# mbmc_single_board_cpu.net
KiCad netlist of a schematic drawn in EAGLE
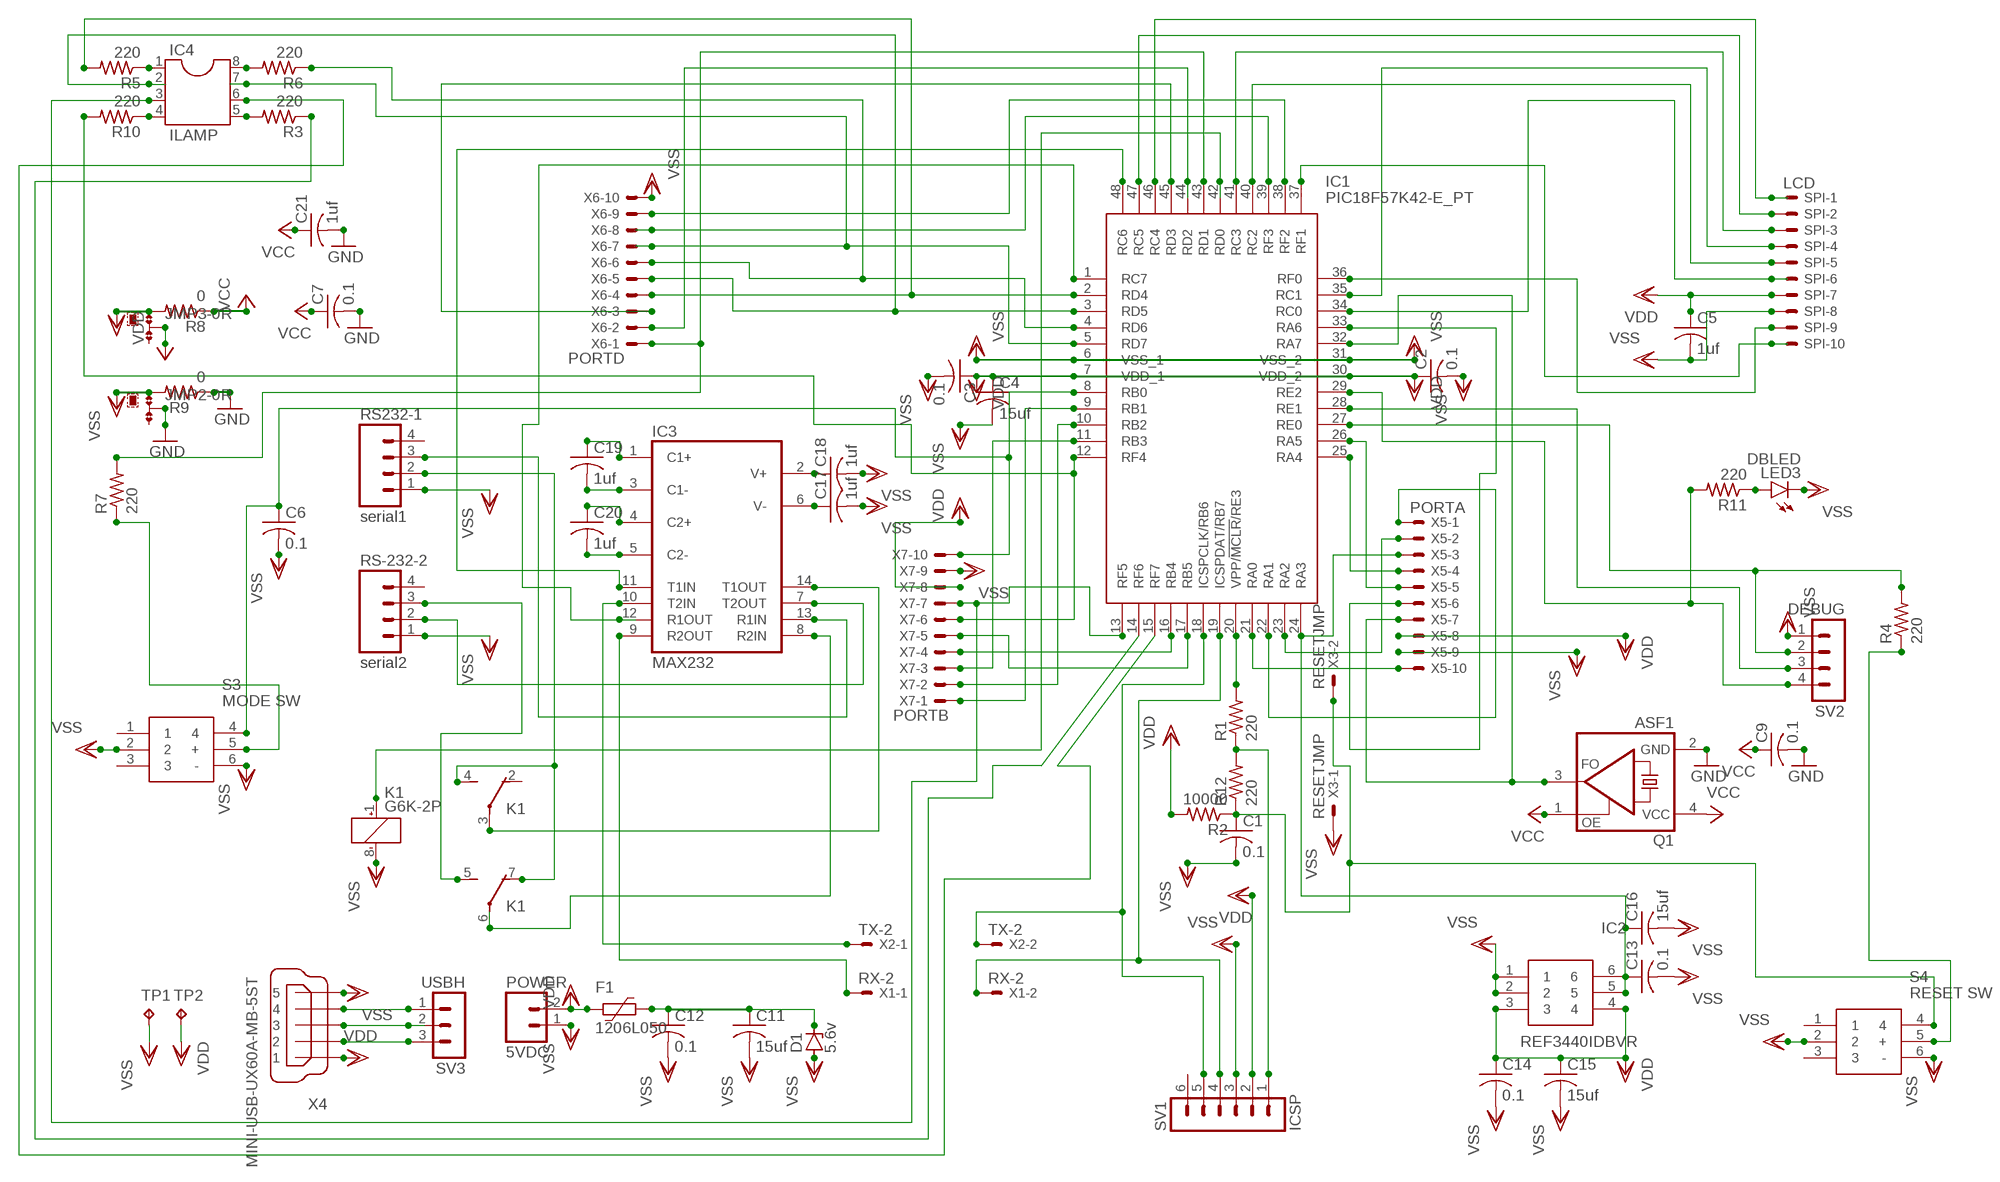
[diagram p0: schematic, sheet 1]

(export (version "E")
  (design (tool "Eeschema 10.0.6"))
  (components
    (comp (ref "C1")
      (value "0.1")
      (footprint "eagle-import:C1206")
      (libsource (lib "eagle-import") (part "C-USC1206"))
    )
    (comp (ref "C2")
      (value "0.1")
      (footprint "eagle-import:C1206")
      (libsource (lib "eagle-import") (part "C-USC1206"))
    )
    (comp (ref "C3")
      (value "0.1")
      (footprint "eagle-import:C1206")
      (libsource (lib "eagle-import") (part "C-USC1206"))
    )
    (comp (ref "C4")
      (value "15uf")
      (footprint "eagle-import:C1206")
      (libsource (lib "eagle-import") (part "C-USC1206"))
    )
    (comp (ref "C5")
      (value "1uf")
      (footprint "eagle-import:C0805")
      (libsource (lib "eagle-import") (part "C-USC0805"))
    )
    (comp (ref "C6")
      (value "0.1")
      (footprint "eagle-import:C1206")
      (libsource (lib "eagle-import") (part "C-USC1206"))
    )
    (comp (ref "C7")
      (value "0.1")
      (footprint "eagle-import:C1206")
      (libsource (lib "eagle-import") (part "C-USC1206"))
    )
    (comp (ref "C9")
      (value "0.1")
      (footprint "eagle-import:C1206")
      (libsource (lib "eagle-import") (part "C-USC1206"))
    )
    (comp (ref "C11")
      (value "15uf")
      (footprint "eagle-import:C1206")
      (libsource (lib "eagle-import") (part "C-USC1206"))
    )
    (comp (ref "C12")
      (value "0.1")
      (footprint "eagle-import:C1206")
      (libsource (lib "eagle-import") (part "C-USC1206"))
    )
    (comp (ref "C13")
      (value "0.1")
      (footprint "eagle-import:C1206")
      (libsource (lib "eagle-import") (part "C-USC1206"))
    )
    (comp (ref "C14")
      (value "0.1")
      (footprint "eagle-import:C1206")
      (libsource (lib "eagle-import") (part "C-USC1206"))
    )
    (comp (ref "C15")
      (value "15uf")
      (footprint "eagle-import:C1206")
      (libsource (lib "eagle-import") (part "C-USC1206"))
    )
    (comp (ref "C16")
      (value "15uf")
      (footprint "eagle-import:C1206")
      (libsource (lib "eagle-import") (part "C-USC1206"))
    )
    (comp (ref "C17")
      (value "1uf")
      (footprint "eagle-import:C0805")
      (libsource (lib "eagle-import") (part "C-USC0805"))
    )
    (comp (ref "C18")
      (value "1uf")
      (footprint "eagle-import:C0805")
      (libsource (lib "eagle-import") (part "C-USC0805"))
    )
    (comp (ref "C19")
      (value "1uf")
      (footprint "eagle-import:C0805")
      (libsource (lib "eagle-import") (part "C-USC0805"))
    )
    (comp (ref "C20")
      (value "1uf")
      (footprint "eagle-import:C0805")
      (libsource (lib "eagle-import") (part "C-USC0805"))
    )
    (comp (ref "C21")
      (value "1uf")
      (footprint "eagle-import:C0805")
      (libsource (lib "eagle-import") (part "C-USC0805"))
    )
    (comp (ref "D1")
      (value "5.6v")
      (footprint "eagle-import:DO34Z7")
      (libsource (lib "eagle-import") (part "ZENER-DIODEDO34-7"))
    )
    (comp (ref "F1")
      (value "1206L050")
      (footprint "eagle-import:1206L")
      (fields (field (name "MF") "Littelfuse"))
      (libsource (lib "eagle-import") (part "?1206L050"))
    )
    (comp (ref "IC1")
      (value "PIC18F57K42-E_PT")
      (footprint "eagle-import:QFP50P900X900X120-48N")
      (fields
        (field (name "MANUFACTURER_PART_NUMBER") "PIC18F57K42-E/PT")
        (field (name "MOUSER_PART_NUMBER") "579-PIC18F57K42-E/PT")
      )
      (libsource (lib "eagle-import") (part "PIC18F57K42-E_PT"))
    )
    (comp (ref "IC2")
      (value "REF3440IDBVR")
      (footprint "eagle-import:SOP95P280X145-6N")
      (libsource (lib "eagle-import") (part "REF3440IDBVR"))
    )
    (comp (ref "IC3")
      (value "MAX232")
      (footprint "eagle-import:DIL16")
      (fields (field (name "MF") "MAXIM") (field (name "MPN") "MAX232ACPE+"))
      (libsource (lib "eagle-import") (part "MAX232"))
    )
    (comp (ref "IC4")
      (value "ILAMP")
      (footprint "eagle-import:SOCKET-08")
      (libsource (lib "eagle-import") (part "DIL8S"))
    )
    (comp (ref "JMP2")
      (value "0R-JUMPA")
      (footprint "eagle-import:A0R-JMP")
      (libsource (lib "eagle-import") (part "0R-JUMPA"))
    )
    (comp (ref "JMP3")
      (value "0R-JUMPA")
      (footprint "eagle-import:A0R-JMP")
      (libsource (lib "eagle-import") (part "0R-JUMPA"))
    )
    (comp (ref "K1")
      (value "G6K-2P")
      (footprint "eagle-import:G6K-2P")
      (fields (field (name "MF") "OMRON COMPONENTS USA") (field (name "MPN") "G6K-2P DC3"))
      (libsource (lib "eagle-import") (part "G6K-2P"))
    )
    (comp (ref "LED3")
      (value "DBLED")
      (footprint "eagle-import:CHIPLED_1206")
      (libsource (lib "eagle-import") (part "LEDCHIPLED_1206"))
    )
    (comp (ref "POWER")
      (value "5VDC")
      (footprint "eagle-import:02P")
      (libsource (lib "eagle-import") (part "M02"))
    )
    (comp (ref "Q1")
      (value "ASF1")
      (footprint "eagle-import:ASF")
      (libsource (lib "eagle-import") (part "ASF1"))
    )
    (comp (ref "R1")
      (value "220")
      (footprint "eagle-import:R1206")
      (libsource (lib "eagle-import") (part "R-US_R1206"))
    )
    (comp (ref "R2")
      (value "10000")
      (footprint "eagle-import:R1206")
      (libsource (lib "eagle-import") (part "R-US_R1206"))
    )
    (comp (ref "R3")
      (value "220")
      (footprint "eagle-import:R1206")
      (libsource (lib "eagle-import") (part "R-US_R1206"))
    )
    (comp (ref "R4")
      (value "220")
      (footprint "eagle-import:R1206")
      (libsource (lib "eagle-import") (part "R-US_R1206"))
    )
    (comp (ref "R5")
      (value "220")
      (footprint "eagle-import:R1206")
      (libsource (lib "eagle-import") (part "R-US_R1206"))
    )
    (comp (ref "R6")
      (value "220")
      (footprint "eagle-import:R1206")
      (libsource (lib "eagle-import") (part "R-US_R1206"))
    )
    (comp (ref "R7")
      (value "220")
      (footprint "eagle-import:R1206")
      (libsource (lib "eagle-import") (part "R-US_R1206"))
    )
    (comp (ref "R8")
      (value "0")
      (footprint "eagle-import:R1206")
      (libsource (lib "eagle-import") (part "R-US_R1206"))
    )
    (comp (ref "R9")
      (value "0")
      (footprint "eagle-import:R1206")
      (libsource (lib "eagle-import") (part "R-US_R1206"))
    )
    (comp (ref "R10")
      (value "220")
      (footprint "eagle-import:R1206")
      (libsource (lib "eagle-import") (part "R-US_R1206"))
    )
    (comp (ref "R11")
      (value "220")
      (footprint "eagle-import:R1206")
      (libsource (lib "eagle-import") (part "R-US_R1206"))
    )
    (comp (ref "R12")
      (value "220")
      (footprint "eagle-import:R1206")
      (libsource (lib "eagle-import") (part "R-US_R1206"))
    )
    (comp (ref "RS-232-2")
      (value "serial2")
      (footprint "eagle-import:04P")
      (libsource (lib "eagle-import") (part "M04"))
    )
    (comp (ref "RS232-1")
      (value "serial1")
      (footprint "eagle-import:04P")
      (libsource (lib "eagle-import") (part "M04"))
    )
    (comp (ref "S3")
      (value "MODE SW")
      (footprint "eagle-import:B3W-9_1-LED")
      (fields
        (field (name "MANUFACTURER_PART_NUMBER") "B3W-9000-Y1N")
        (field (name "MOUSER_PART_NUMBER") "653-B3W-9000-Y1N")
        (field (name "RS_PART_NUMBER") "0492777P")
      )
      (libsource (lib "eagle-import") (part "B3W-9000-Y1N"))
    )
    (comp (ref "S4")
      (value "RESET SW")
      (footprint "eagle-import:B3W-9_1-LED")
      (fields
        (field (name "MANUFACTURER_PART_NUMBER") "B3W-9000-Y1N")
        (field (name "MOUSER_PART_NUMBER") "653-B3W-9000-Y1N")
        (field (name "RS_PART_NUMBER") "0492777P")
      )
      (libsource (lib "eagle-import") (part "B3W-9000-Y1N"))
    )
    (comp (ref "SPI")
      (value "LCD")
      (footprint "eagle-import:22-23-2101")
      (fields (field (name "MF") "MOLEX") (field (name "MPN") "22-23-2101"))
      (libsource (lib "eagle-import") (part "22-23-2101"))
    )
    (comp (ref "SV1")
      (value "ICSP")
      (footprint "eagle-import:MA06-1")
      (libsource (lib "eagle-import") (part "MA06-1"))
    )
    (comp (ref "SV2")
      (value "DEBUG")
      (footprint "eagle-import:MA04-1")
      (libsource (lib "eagle-import") (part "MA04-1"))
    )
    (comp (ref "SV3")
      (value "USBH")
      (footprint "eagle-import:MA03-1")
      (libsource (lib "eagle-import") (part "MA03-1"))
    )
    (comp (ref "TP1")
      (value "TPB1,27")
      (footprint "eagle-import:B1,27")
      (libsource (lib "eagle-import") (part "TPB1,27"))
    )
    (comp (ref "TP2")
      (value "TPB1,27")
      (footprint "eagle-import:B1,27")
      (libsource (lib "eagle-import") (part "TPB1,27"))
    )
    (comp (ref "X1")
      (value "RX-2")
      (footprint "eagle-import:332-02")
      (libsource (lib "eagle-import") (part "332-02"))
    )
    (comp (ref "X2")
      (value "TX-2")
      (footprint "eagle-import:332-02")
      (libsource (lib "eagle-import") (part "332-02"))
    )
    (comp (ref "X3")
      (value "RESETJMP")
      (footprint "eagle-import:332-02")
      (libsource (lib "eagle-import") (part "332-02"))
    )
    (comp (ref "X4")
      (value "MINI-USB-UX60A-MB-5ST")
      (footprint "eagle-import:UX60A-MB-5ST")
      (libsource (lib "eagle-import") (part "MINI-USB-UX60A-MB-5ST"))
    )
    (comp (ref "X5")
      (value "PORTA")
      (footprint "eagle-import:22-23-2101")
      (fields (field (name "MF") "MOLEX") (field (name "MPN") "22-23-2101"))
      (libsource (lib "eagle-import") (part "22-23-2101"))
    )
    (comp (ref "X6")
      (value "PORTD")
      (footprint "eagle-import:22-23-2101")
      (fields (field (name "MF") "MOLEX") (field (name "MPN") "22-23-2101"))
      (libsource (lib "eagle-import") (part "22-23-2101"))
    )
    (comp (ref "X7")
      (value "PORTB")
      (footprint "eagle-import:22-23-2101")
      (fields (field (name "MF") "MOLEX") (field (name "MPN") "22-23-2101"))
      (libsource (lib "eagle-import") (part "22-23-2101"))
    )
  )
  (nets
    (net (code "1") (name "GND") (class "Default")
      (node (ref "C21") (pin "2") (pinfunction "2_2") (pintype "passive"))
      (node (ref "C7") (pin "2") (pinfunction "2_2") (pintype "passive"))
      (node (ref "C9") (pin "2") (pinfunction "2_2") (pintype "passive"))
      (node (ref "JMP2") (pin "2") (pinfunction "2_2") (pintype "passive"))
      (node (ref "Q1") (pin "2") (pinfunction "GND_2") (pintype "power_in"))
      (node (ref "R9") (pin "1") (pinfunction "1_1") (pintype "passive"))
    )
    (net (code "2") (name "Net-(C11-Pad1)") (class "Default")
      (node (ref "C11") (pin "1") (pinfunction "1_1") (pintype "passive"))
      (node (ref "C12") (pin "1") (pinfunction "1_1") (pintype "passive"))
      (node (ref "D1") (pin "C") (pinfunction "C_C") (pintype "passive"))
      (node (ref "F1") (pin "1") (pinfunction "1_1") (pintype "passive"))
    )
    (net (code "3") (name "Net-(IC1-ICSPCLK{slash}RB6)") (class "Default")
      (node (ref "IC1") (pin "18") (pinfunction "ICSPCLK/RB6_18") (pintype "bidirectional"))
      (node (ref "SV1") (pin "5") (pinfunction "5_5") (pintype "passive"))
      (node (ref "X2") (pin "2") (pinfunction "S_2") (pintype "passive"))
    )
    (net (code "4") (name "Net-(IC1-ICSPDAT{slash}RB7)") (class "Default")
      (node (ref "IC1") (pin "19") (pinfunction "ICSPDAT/RB7_19") (pintype "bidirectional"))
      (node (ref "SV1") (pin "4") (pinfunction "4_4") (pintype "passive"))
      (node (ref "X1") (pin "2") (pinfunction "S_2") (pintype "passive"))
    )
    (net (code "5") (name "Net-(IC1-RA0)") (class "Default")
      (node (ref "IC1") (pin "21") (pinfunction "RA0_21") (pintype "bidirectional"))
      (node (ref "X5") (pin "10") (pinfunction "S_10") (pintype "passive"))
    )
    (net (code "6") (name "Net-(IC1-RA1)") (class "Default")
      (node (ref "IC1") (pin "22") (pinfunction "RA1_22") (pintype "bidirectional"))
      (node (ref "X5") (pin "1") (pinfunction "S_1") (pintype "passive"))
    )
    (net (code "7") (name "Net-(IC1-RA2)") (class "Default")
      (node (ref "IC1") (pin "23") (pinfunction "RA2_23") (pintype "bidirectional"))
      (node (ref "X5") (pin "2") (pinfunction "S_2") (pintype "passive"))
    )
    (net (code "8") (name "Net-(IC1-RA3)") (class "Default")
      (node (ref "C13") (pin "1") (pinfunction "1_1") (pintype "passive"))
      (node (ref "C16") (pin "1") (pinfunction "1_1") (pintype "passive"))
      (node (ref "IC1") (pin "24") (pinfunction "RA3_24") (pintype "bidirectional"))
      (node (ref "IC2") (pin "5") (pinfunction "5_5") (pintype "bidirectional"))
      (node (ref "IC2") (pin "6") (pinfunction "6_6") (pintype "bidirectional"))
      (node (ref "X5") (pin "3") (pinfunction "S_3") (pintype "passive"))
    )
    (net (code "9") (name "Net-(IC1-RA4)") (class "Default")
      (node (ref "IC1") (pin "25") (pinfunction "RA4_25") (pintype "bidirectional"))
      (node (ref "X5") (pin "4") (pinfunction "S_4") (pintype "passive"))
    )
    (net (code "10") (name "Net-(IC1-RA5)") (class "Default")
      (node (ref "IC1") (pin "26") (pinfunction "RA5_26") (pintype "bidirectional"))
      (node (ref "X5") (pin "5") (pinfunction "S_5") (pintype "passive"))
    )
    (net (code "11") (name "Net-(IC1-RA6)") (class "Default")
      (node (ref "IC1") (pin "33") (pinfunction "RA6_33") (pintype "bidirectional"))
      (node (ref "X5") (pin "6") (pinfunction "S_6") (pintype "passive"))
    )
    (net (code "12") (name "Net-(IC1-RA7)") (class "Default")
      (node (ref "IC1") (pin "32") (pinfunction "RA7_32") (pintype "bidirectional"))
      (node (ref "Q1") (pin "3") (pinfunction "FO_3") (pintype "output"))
      (node (ref "X5") (pin "7") (pinfunction "S_7") (pintype "passive"))
    )
    (net (code "13") (name "Net-(IC1-RB0)") (class "Default")
      (node (ref "C6") (pin "1") (pinfunction "1_1") (pintype "passive"))
      (node (ref "IC1") (pin "8") (pinfunction "RB0_8") (pintype "bidirectional"))
      (node (ref "S3") (pin "4") (pinfunction "4_4") (pintype "bidirectional"))
      (node (ref "X7") (pin "10") (pinfunction "S_10") (pintype "passive"))
    )
    (net (code "14") (name "Net-(IC1-RB1)") (class "Default")
      (node (ref "IC1") (pin "9") (pinfunction "RB1_9") (pintype "bidirectional"))
      (node (ref "X7") (pin "1") (pinfunction "S_1") (pintype "passive"))
    )
    (net (code "15") (name "Net-(IC1-RB2)") (class "Default")
      (node (ref "IC1") (pin "10") (pinfunction "RB2_10") (pintype "bidirectional"))
      (node (ref "X7") (pin "2") (pinfunction "S_2") (pintype "passive"))
    )
    (net (code "16") (name "Net-(IC1-RB3)") (class "Default")
      (node (ref "IC1") (pin "11") (pinfunction "RB3_11") (pintype "bidirectional"))
      (node (ref "X7") (pin "3") (pinfunction "S_3") (pintype "passive"))
    )
    (net (code "17") (name "Net-(IC1-RB4)") (class "Default")
      (node (ref "IC1") (pin "16") (pinfunction "RB4_16") (pintype "bidirectional"))
      (node (ref "X7") (pin "4") (pinfunction "S_4") (pintype "passive"))
    )
    (net (code "18") (name "Net-(IC1-RB5)") (class "Default")
      (node (ref "IC1") (pin "17") (pinfunction "RB5_17") (pintype "bidirectional"))
      (node (ref "X7") (pin "5") (pinfunction "S_5") (pintype "passive"))
    )
    (net (code "19") (name "Net-(IC1-RC0)") (class "Default")
      (node (ref "IC1") (pin "34") (pinfunction "RC0_34") (pintype "bidirectional"))
      (node (ref "SPI") (pin "6") (pinfunction "S_6") (pintype "passive"))
    )
    (net (code "20") (name "Net-(IC1-RC1)") (class "Default")
      (node (ref "IC1") (pin "35") (pinfunction "RC1_35") (pintype "bidirectional"))
      (node (ref "SPI") (pin "4") (pinfunction "S_4") (pintype "passive"))
    )
    (net (code "21") (name "Net-(IC1-RC2)") (class "Default")
      (node (ref "IC1") (pin "40") (pinfunction "RC2_40") (pintype "bidirectional"))
      (node (ref "SPI") (pin "5") (pinfunction "S_5") (pintype "passive"))
    )
    (net (code "22") (name "Net-(IC1-RC3)") (class "Default")
      (node (ref "IC1") (pin "41") (pinfunction "RC3_41") (pintype "bidirectional"))
      (node (ref "SPI") (pin "3") (pinfunction "S_3") (pintype "passive"))
    )
    (net (code "23") (name "Net-(IC1-RC4)") (class "Default")
      (node (ref "IC1") (pin "46") (pinfunction "RC4_46") (pintype "bidirectional"))
      (node (ref "SPI") (pin "1") (pinfunction "S_1") (pintype "passive"))
    )
    (net (code "24") (name "Net-(IC1-RC5)") (class "Default")
      (node (ref "IC1") (pin "47") (pinfunction "RC5_47") (pintype "bidirectional"))
      (node (ref "SPI") (pin "2") (pinfunction "S_2") (pintype "passive"))
    )
    (net (code "25") (name "Net-(IC1-RC6)") (class "Default")
      (node (ref "IC1") (pin "48") (pinfunction "RC6_48") (pintype "bidirectional"))
      (node (ref "IC3") (pin "11") (pinfunction "T1IN_11") (pintype "input"))
    )
    (net (code "26") (name "Net-(IC1-RC7)") (class "Default")
      (node (ref "IC1") (pin "1") (pinfunction "RC7_1") (pintype "bidirectional"))
      (node (ref "IC3") (pin "12") (pinfunction "R1OUT_12") (pintype "output"))
    )
    (net (code "27") (name "Net-(IC1-RD0)") (class "Default")
      (node (ref "IC1") (pin "42") (pinfunction "RD0_42") (pintype "bidirectional"))
      (node (ref "K1") (pin "1") (pinfunction "+_1") (pintype "passive"))
    )
    (net (code "28") (name "Net-(IC1-RD1)") (class "Default")
      (node (ref "IC1") (pin "43") (pinfunction "RD1_43") (pintype "bidirectional"))
      (node (ref "R7") (pin "2") (pinfunction "2_2") (pintype "passive"))
      (node (ref "X6") (pin "1") (pinfunction "S_1") (pintype "passive"))
    )
    (net (code "29") (name "Net-(IC1-RD2)") (class "Default")
      (node (ref "IC1") (pin "44") (pinfunction "RD2_44") (pintype "bidirectional"))
      (node (ref "X6") (pin "2") (pinfunction "S_2") (pintype "passive"))
    )
    (net (code "30") (name "Net-(IC1-RD3)") (class "Default")
      (node (ref "IC1") (pin "45") (pinfunction "RD3_45") (pintype "bidirectional"))
      (node (ref "X6") (pin "3") (pinfunction "S_3") (pintype "passive"))
    )
    (net (code "31") (name "Net-(IC1-RD4)") (class "Default")
      (node (ref "IC1") (pin "2") (pinfunction "RD4_2") (pintype "bidirectional"))
      (node (ref "R5") (pin "2") (pinfunction "2_2") (pintype "passive"))
      (node (ref "X6") (pin "4") (pinfunction "S_4") (pintype "passive"))
    )
    (net (code "32") (name "Net-(IC1-RD5)") (class "Default")
      (node (ref "IC1") (pin "3") (pinfunction "RD5_3") (pintype "bidirectional"))
      (node (ref "IC4") (pin "2") (pinfunction "2_2") (pintype "passive"))
      (node (ref "X6") (pin "5") (pinfunction "S_5") (pintype "passive"))
    )
    (net (code "33") (name "Net-(IC1-RD6)") (class "Default")
      (node (ref "IC1") (pin "4") (pinfunction "RD6_4") (pintype "bidirectional"))
      (node (ref "R6") (pin "1") (pinfunction "1_1") (pintype "passive"))
      (node (ref "X6") (pin "6") (pinfunction "S_6") (pintype "passive"))
    )
    (net (code "34") (name "Net-(IC1-RD7)") (class "Default")
      (node (ref "IC1") (pin "5") (pinfunction "RD7_5") (pintype "bidirectional"))
      (node (ref "IC4") (pin "7") (pinfunction "7_7") (pintype "passive"))
      (node (ref "X6") (pin "7") (pinfunction "S_7") (pintype "passive"))
    )
    (net (code "35") (name "Net-(IC1-RE0)") (class "Default")
      (node (ref "IC1") (pin "27") (pinfunction "RE0_27") (pintype "bidirectional"))
      (node (ref "R4") (pin "2") (pinfunction "2_2") (pintype "passive"))
      (node (ref "SV2") (pin "2") (pinfunction "2_2") (pintype "passive"))
    )
    (net (code "36") (name "Net-(IC1-RE1)") (class "Default")
      (node (ref "IC1") (pin "28") (pinfunction "RE1_28") (pintype "bidirectional"))
      (node (ref "SV2") (pin "3") (pinfunction "3_3") (pintype "passive"))
    )
    (net (code "37") (name "Net-(IC1-RE2)") (class "Default")
      (node (ref "IC1") (pin "29") (pinfunction "RE2_29") (pintype "bidirectional"))
      (node (ref "R11") (pin "2") (pinfunction "2_2") (pintype "passive"))
      (node (ref "SV2") (pin "4") (pinfunction "4_4") (pintype "passive"))
    )
    (net (code "38") (name "Net-(IC1-RF0)") (class "Default")
      (node (ref "IC1") (pin "36") (pinfunction "RF0_36") (pintype "bidirectional"))
      (node (ref "SPI") (pin "9") (pinfunction "S_9") (pintype "passive"))
    )
    (net (code "39") (name "Net-(IC1-RF1)") (class "Default")
      (node (ref "IC1") (pin "37") (pinfunction "RF1_37") (pintype "bidirectional"))
      (node (ref "SPI") (pin "10") (pinfunction "S_10") (pintype "passive"))
    )
    (net (code "40") (name "Net-(IC1-RF2)") (class "Default")
      (node (ref "IC1") (pin "38") (pinfunction "RF2_38") (pintype "bidirectional"))
      (node (ref "X6") (pin "9") (pinfunction "S_9") (pintype "passive"))
    )
    (net (code "41") (name "Net-(IC1-RF3)") (class "Default")
      (node (ref "IC1") (pin "39") (pinfunction "RF3_39") (pintype "bidirectional"))
      (node (ref "X6") (pin "8") (pinfunction "S_8") (pintype "passive"))
    )
    (net (code "42") (name "Net-(IC1-RF4)") (class "Default")
      (node (ref "IC1") (pin "12") (pinfunction "RF4_12") (pintype "bidirectional"))
      (node (ref "R10") (pin "2") (pinfunction "2_2") (pintype "passive"))
      (node (ref "X7") (pin "6") (pinfunction "S_6") (pintype "passive"))
    )
    (net (code "43") (name "Net-(IC1-RF5)") (class "Default")
      (node (ref "IC1") (pin "13") (pinfunction "RF5_13") (pintype "bidirectional"))
      (node (ref "IC4") (pin "3") (pinfunction "3_3") (pintype "passive"))
      (node (ref "X7") (pin "7") (pinfunction "S_7") (pintype "passive"))
    )
    (net (code "44") (name "Net-(IC1-RF6)") (class "Default")
      (node (ref "IC1") (pin "14") (pinfunction "RF6_14") (pintype "bidirectional"))
      (node (ref "R3") (pin "1") (pinfunction "1_1") (pintype "passive"))
    )
    (net (code "45") (name "Net-(IC1-RF7)") (class "Default")
      (node (ref "IC1") (pin "15") (pinfunction "RF7_15") (pintype "bidirectional"))
      (node (ref "IC4") (pin "6") (pinfunction "6_6") (pintype "passive"))
    )
    (net (code "46") (name "Net-(IC1-VPP{slash}~{MCLR}{slash}RE3)") (class "Default")
      (node (ref "IC1") (pin "20") (pinfunction "VPP/~{MCLR}/RE3_20") (pintype "bidirectional"))
      (node (ref "R1") (pin "2") (pinfunction "2_2") (pintype "passive"))
    )
    (net (code "47") (name "Net-(IC3A-C1+)") (class "Default")
      (node (ref "C19") (pin "1") (pinfunction "1_1") (pintype "passive"))
      (node (ref "IC3") (pin "1") (pinfunction "C1+_1") (pintype "bidirectional"))
    )
    (net (code "48") (name "Net-(IC3A-C1-)") (class "Default")
      (node (ref "C19") (pin "2") (pinfunction "2_2") (pintype "passive"))
      (node (ref "IC3") (pin "3") (pinfunction "C1-_3") (pintype "bidirectional"))
    )
    (net (code "49") (name "Net-(IC3A-C2+)") (class "Default")
      (node (ref "C20") (pin "1") (pinfunction "1_1") (pintype "passive"))
      (node (ref "IC3") (pin "4") (pinfunction "C2+_4") (pintype "bidirectional"))
    )
    (net (code "50") (name "Net-(IC3A-C2-)") (class "Default")
      (node (ref "C20") (pin "2") (pinfunction "2_2") (pintype "passive"))
      (node (ref "IC3") (pin "5") (pinfunction "C2-_5") (pintype "bidirectional"))
    )
    (net (code "51") (name "Net-(IC3A-R1IN)") (class "Default")
      (node (ref "IC3") (pin "13") (pinfunction "R1IN_13") (pintype "input"))
      (node (ref "RS232-1") (pin "3") (pinfunction "3_3") (pintype "passive"))
    )
    (net (code "52") (name "Net-(IC3A-R2IN)") (class "Default")
      (node (ref "IC3") (pin "8") (pinfunction "R2IN_8") (pintype "input"))
      (node (ref "K1") (pin "6") (pinfunction "P_6") (pintype "passive"))
    )
    (net (code "53") (name "Net-(IC3A-R2OUT)") (class "Default")
      (node (ref "IC3") (pin "9") (pinfunction "R2OUT_9") (pintype "output"))
      (node (ref "X1") (pin "1") (pinfunction "S_1") (pintype "passive"))
    )
    (net (code "54") (name "Net-(IC3A-T1OUT)") (class "Default")
      (node (ref "IC3") (pin "14") (pinfunction "T1OUT_14") (pintype "output"))
      (node (ref "K1") (pin "3") (pinfunction "P_3") (pintype "passive"))
    )
    (net (code "55") (name "Net-(IC3A-T2IN)") (class "Default")
      (node (ref "IC3") (pin "10") (pinfunction "T2IN_10") (pintype "input"))
      (node (ref "X2") (pin "1") (pinfunction "S_1") (pintype "passive"))
    )
    (net (code "56") (name "Net-(IC3A-T2OUT)") (class "Default")
      (node (ref "IC3") (pin "7") (pinfunction "T2OUT_7") (pintype "output"))
      (node (ref "RS-232-2") (pin "2") (pinfunction "2_2") (pintype "passive"))
    )
    (net (code "57") (name "Net-(IC3A-V+)") (class "Default")
      (node (ref "C18") (pin "1") (pinfunction "1_1") (pintype "passive"))
      (node (ref "IC3") (pin "2") (pinfunction "V+_2") (pintype "bidirectional"))
    )
    (net (code "58") (name "Net-(IC3A-V-)") (class "Default")
      (node (ref "C17") (pin "1") (pinfunction "1_1") (pintype "passive"))
      (node (ref "IC3") (pin "6") (pinfunction "V-_6") (pintype "bidirectional"))
    )
    (net (code "59") (name "Net-(IC4-Pad1)") (class "Default")
      (node (ref "IC4") (pin "1") (pinfunction "1_1") (pintype "passive"))
      (node (ref "R5") (pin "1") (pinfunction "1_1") (pintype "passive"))
    )
    (net (code "60") (name "Net-(IC4-Pad4)") (class "Default")
      (node (ref "IC4") (pin "4") (pinfunction "4_4") (pintype "passive"))
      (node (ref "R10") (pin "1") (pinfunction "1_1") (pintype "passive"))
    )
    (net (code "61") (name "Net-(IC4-Pad5)") (class "Default")
      (node (ref "IC4") (pin "5") (pinfunction "5_5") (pintype "passive"))
      (node (ref "R3") (pin "2") (pinfunction "2_2") (pintype "passive"))
    )
    (net (code "62") (name "Net-(IC4-Pad8)") (class "Default")
      (node (ref "IC4") (pin "8") (pinfunction "8_8") (pintype "passive"))
      (node (ref "R6") (pin "2") (pinfunction "2_2") (pintype "passive"))
    )
    (net (code "63") (name "Net-(K1B-S)") (class "Default")
      (node (ref "K1") (pin "4") (pinfunction "S_4") (pintype "passive"))
      (node (ref "K1") (pin "7") (pinfunction "O_7") (pintype "passive"))
      (node (ref "RS232-1") (pin "2") (pinfunction "2_2") (pintype "passive"))
    )
    (net (code "64") (name "Net-(K1C-S)") (class "Default")
      (node (ref "K1") (pin "5") (pinfunction "S_5") (pintype "passive"))
      (node (ref "RS-232-2") (pin "3") (pinfunction "3_3") (pintype "passive"))
    )
    (net (code "65") (name "Net-(LED3-PadA)") (class "Default")
      (node (ref "LED3") (pin "A") (pinfunction "A_A") (pintype "passive"))
      (node (ref "R11") (pin "1") (pinfunction "1_1") (pintype "passive"))
    )
    (net (code "66") (name "Net-(R1-Pad1)") (class "Default")
      (node (ref "R1") (pin "1") (pinfunction "1_1") (pintype "passive"))
      (node (ref "R12") (pin "2") (pinfunction "2_2") (pintype "passive"))
      (node (ref "SV1") (pin "1") (pinfunction "1_1") (pintype "passive"))
    )
    (net (code "67") (name "Net-(S3-+)") (class "Default")
      (node (ref "R7") (pin "1") (pinfunction "1_1") (pintype "passive"))
      (node (ref "S3") (pin "5") (pinfunction "+_5") (pintype "bidirectional"))
    )
    (net (code "68") (name "Net-(S4-+)") (class "Default")
      (node (ref "R4") (pin "1") (pinfunction "1_1") (pintype "passive"))
      (node (ref "S4") (pin "5") (pinfunction "+_5") (pintype "bidirectional"))
    )
    (net (code "69") (name "Net-(SV3-Pad1)") (class "Default")
      (node (ref "SV3") (pin "1") (pinfunction "1_1") (pintype "passive"))
      (node (ref "X4") (pin "4") (pinfunction "4_4") (pintype "input"))
    )
    (net (code "70") (name "Net-(SV3-Pad2)") (class "Default")
      (node (ref "SV3") (pin "2") (pinfunction "2_2") (pintype "passive"))
      (node (ref "X4") (pin "3") (pinfunction "3_3") (pintype "input"))
    )
    (net (code "71") (name "Net-(SV3-Pad3)") (class "Default")
      (node (ref "SV3") (pin "3") (pinfunction "3_3") (pintype "passive"))
      (node (ref "X4") (pin "2") (pinfunction "2_2") (pintype "input"))
    )
    (net (code "72") (name "Net-(X3B-S)") (class "Default")
      (node (ref "C1") (pin "1") (pinfunction "1_1") (pintype "passive"))
      (node (ref "R12") (pin "1") (pinfunction "1_1") (pintype "passive"))
      (node (ref "R2") (pin "1") (pinfunction "1_1") (pintype "passive"))
      (node (ref "S4") (pin "4") (pinfunction "4_4") (pintype "bidirectional"))
      (node (ref "X3") (pin "2") (pinfunction "S_2") (pintype "passive"))
    )
    (net (code "73") (name "VCC") (class "Default")
      (node (ref "C21") (pin "1") (pinfunction "1_1") (pintype "passive"))
      (node (ref "C7") (pin "1") (pinfunction "1_1") (pintype "passive"))
      (node (ref "C9") (pin "1") (pinfunction "1_1") (pintype "passive"))
      (node (ref "JMP3") (pin "2") (pinfunction "2_2") (pintype "passive"))
      (node (ref "Q1") (pin "1") (pinfunction "OE_1") (pintype "input"))
      (node (ref "Q1") (pin "4") (pinfunction "VCC_4") (pintype "power_in"))
      (node (ref "R8") (pin "1") (pinfunction "1_1") (pintype "passive"))
    )
    (net (code "74") (name "VDD") (class "Default")
      (node (ref "C14") (pin "1") (pinfunction "1_1") (pintype "passive"))
      (node (ref "C15") (pin "1") (pinfunction "1_1") (pintype "passive"))
      (node (ref "C2") (pin "1") (pinfunction "1_1") (pintype "passive"))
      (node (ref "C3") (pin "1") (pinfunction "1_1") (pintype "passive"))
      (node (ref "C4") (pin "1") (pinfunction "1_1") (pintype "passive"))
      (node (ref "C5") (pin "1") (pinfunction "1_1") (pintype "passive"))
      (node (ref "F1") (pin "2") (pinfunction "2_2") (pintype "passive"))
      (node (ref "IC1") (pin "30") (pinfunction "VDD_2_30") (pintype "bidirectional"))
      (node (ref "IC1") (pin "7") (pinfunction "VDD_1_7") (pintype "bidirectional"))
      (node (ref "IC2") (pin "3") (pinfunction "3_3") (pintype "bidirectional"))
      (node (ref "IC2") (pin "4") (pinfunction "4_4") (pintype "bidirectional"))
      (node (ref "JMP3") (pin "1") (pinfunction "1_1") (pintype "passive"))
      (node (ref "POWER") (pin "2") (pinfunction "2_2") (pintype "passive"))
      (node (ref "R2") (pin "2") (pinfunction "2_2") (pintype "passive"))
      (node (ref "R8") (pin "2") (pinfunction "2_2") (pintype "passive"))
      (node (ref "SPI") (pin "7") (pinfunction "S_7") (pintype "passive"))
      (node (ref "SV1") (pin "2") (pinfunction "2_2") (pintype "passive"))
      (node (ref "TP2") (pin "TP") (pinfunction "TP_TP") (pintype "input"))
      (node (ref "X4") (pin "1") (pinfunction "1_1") (pintype "input"))
      (node (ref "X5") (pin "8") (pinfunction "S_8") (pintype "passive"))
      (node (ref "X7") (pin "8") (pinfunction "S_8") (pintype "passive"))
    )
    (net (code "75") (name "VSS") (class "Default")
      (node (ref "C1") (pin "2") (pinfunction "2_2") (pintype "passive"))
      (node (ref "C11") (pin "2") (pinfunction "2_2") (pintype "passive"))
      (node (ref "C12") (pin "2") (pinfunction "2_2") (pintype "passive"))
      (node (ref "C13") (pin "2") (pinfunction "2_2") (pintype "passive"))
      (node (ref "C14") (pin "2") (pinfunction "2_2") (pintype "passive"))
      (node (ref "C15") (pin "2") (pinfunction "2_2") (pintype "passive"))
      (node (ref "C16") (pin "2") (pinfunction "2_2") (pintype "passive"))
      (node (ref "C17") (pin "2") (pinfunction "2_2") (pintype "passive"))
      (node (ref "C18") (pin "2") (pinfunction "2_2") (pintype "passive"))
      (node (ref "C2") (pin "2") (pinfunction "2_2") (pintype "passive"))
      (node (ref "C3") (pin "2") (pinfunction "2_2") (pintype "passive"))
      (node (ref "C4") (pin "2") (pinfunction "2_2") (pintype "passive"))
      (node (ref "C5") (pin "2") (pinfunction "2_2") (pintype "passive"))
      (node (ref "C6") (pin "2") (pinfunction "2_2") (pintype "passive"))
      (node (ref "D1") (pin "A") (pinfunction "A_A") (pintype "passive"))
      (node (ref "IC1") (pin "31") (pinfunction "VSS_2_31") (pintype "bidirectional"))
      (node (ref "IC1") (pin "6") (pinfunction "VSS_1_6") (pintype "bidirectional"))
      (node (ref "IC2") (pin "1") (pinfunction "1_1") (pintype "bidirectional"))
      (node (ref "IC2") (pin "2") (pinfunction "2_2") (pintype "bidirectional"))
      (node (ref "JMP2") (pin "1") (pinfunction "1_1") (pintype "passive"))
      (node (ref "K1") (pin "8") (pinfunction "-_8") (pintype "passive"))
      (node (ref "LED3") (pin "C") (pinfunction "C_C") (pintype "passive"))
      (node (ref "POWER") (pin "1") (pinfunction "1_1") (pintype "passive"))
      (node (ref "R9") (pin "2") (pinfunction "2_2") (pintype "passive"))
      (node (ref "RS-232-2") (pin "1") (pinfunction "1_1") (pintype "passive"))
      (node (ref "RS232-1") (pin "1") (pinfunction "1_1") (pintype "passive"))
      (node (ref "S3") (pin "2") (pinfunction "2_2") (pintype "bidirectional"))
      (node (ref "S3") (pin "6") (pinfunction "-_6") (pintype "bidirectional"))
      (node (ref "S4") (pin "2") (pinfunction "2_2") (pintype "bidirectional"))
      (node (ref "S4") (pin "6") (pinfunction "-_6") (pintype "bidirectional"))
      (node (ref "SPI") (pin "8") (pinfunction "S_8") (pintype "passive"))
      (node (ref "SV1") (pin "3") (pinfunction "3_3") (pintype "passive"))
      (node (ref "SV2") (pin "1") (pinfunction "1_1") (pintype "passive"))
      (node (ref "TP1") (pin "TP") (pinfunction "TP_TP") (pintype "input"))
      (node (ref "X3") (pin "1") (pinfunction "S_1") (pintype "passive"))
      (node (ref "X4") (pin "5") (pinfunction "5_5") (pintype "input"))
      (node (ref "X5") (pin "9") (pinfunction "S_9") (pintype "passive"))
      (node (ref "X6") (pin "10") (pinfunction "S_10") (pintype "passive"))
      (node (ref "X7") (pin "9") (pinfunction "S_9") (pintype "passive"))
    )
    (net (code "76") (name "unconnected-(JMP2-Pad3)") (class "Default")
      (node (ref "JMP2") (pin "3") (pinfunction "3_3") (pintype "passive"))
    )
    (net (code "77") (name "unconnected-(JMP3-Pad3)") (class "Default")
      (node (ref "JMP3") (pin "3") (pinfunction "3_3") (pintype "passive"))
    )
    (net (code "78") (name "unconnected-(K1B-O-Pad2)") (class "Default")
      (node (ref "K1") (pin "2") (pinfunction "O_2") (pintype "passive"))
    )
    (net (code "79") (name "unconnected-(RS-232-2-Pad4)") (class "Default")
      (node (ref "RS-232-2") (pin "4") (pinfunction "4_4") (pintype "passive"))
    )
    (net (code "80") (name "unconnected-(RS232-1-Pad4)") (class "Default")
      (node (ref "RS232-1") (pin "4") (pinfunction "4_4") (pintype "passive"))
    )
    (net (code "81") (name "unconnected-(S3-Pad1)") (class "Default")
      (node (ref "S3") (pin "1") (pinfunction "1_1") (pintype "bidirectional"))
    )
    (net (code "82") (name "unconnected-(S3-Pad3)") (class "Default")
      (node (ref "S3") (pin "3") (pinfunction "3_3") (pintype "bidirectional"))
    )
    (net (code "83") (name "unconnected-(S4-Pad1)") (class "Default")
      (node (ref "S4") (pin "1") (pinfunction "1_1") (pintype "bidirectional"))
    )
    (net (code "84") (name "unconnected-(S4-Pad3)") (class "Default")
      (node (ref "S4") (pin "3") (pinfunction "3_3") (pintype "bidirectional"))
    )
    (net (code "85") (name "unconnected-(SV1-Pad6)") (class "Default")
      (node (ref "SV1") (pin "6") (pinfunction "6_6") (pintype "passive"))
    )
  )
)
